# PF4_DSPBypass.net
KiCad netlist of a schematic drawn in Altium Designer
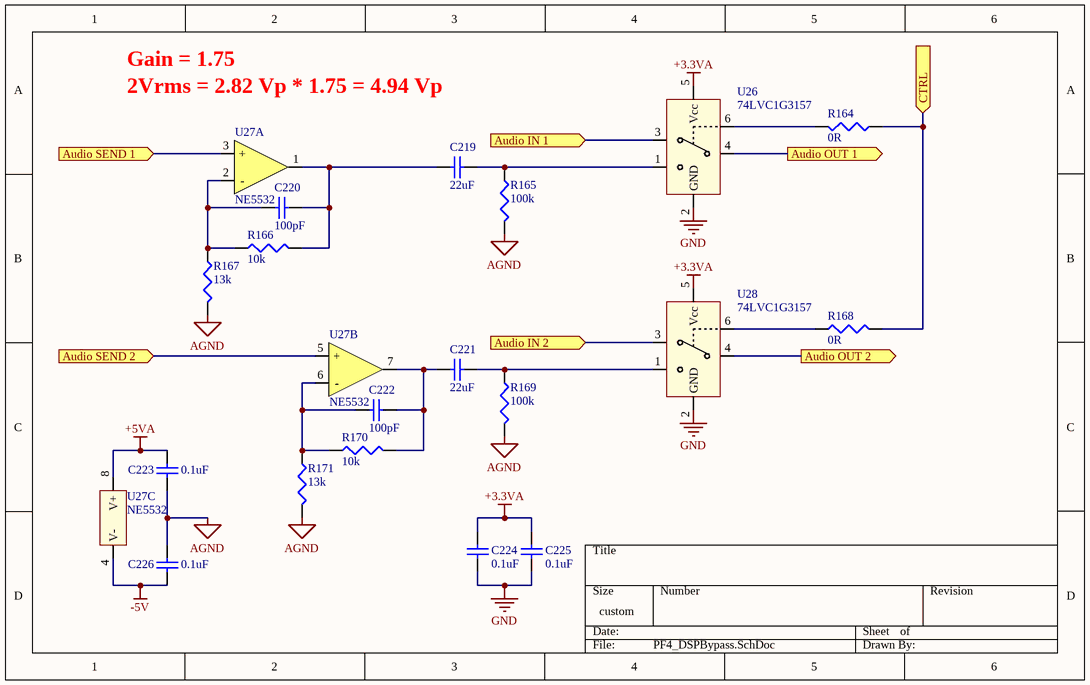
[diagram p0: PF4_DSPBypass.SchDoc]

(export (version "E")
  (design (tool "Eeschema 10.0.6"))
  (components
    (comp (ref "C219")
      (value "22uF")
      (footprint "CAPC1608X08")
      (description "Capacitor (Semiconductor SIM Model)")
      (libsource (lib "Michel") (part "Cap Semi"))
    )
    (comp (ref "C220")
      (value "100pF")
      (footprint "CAPC1608X08")
      (description "Capacitor (Semiconductor SIM Model)")
      (libsource (lib "Michel") (part "Cap Semi"))
    )
    (comp (ref "C221")
      (value "22uF")
      (footprint "CAPC1608X08")
      (description "Capacitor (Semiconductor SIM Model)")
      (libsource (lib "Michel") (part "Cap Semi"))
    )
    (comp (ref "C222")
      (value "100pF")
      (footprint "CAPC1608X08")
      (description "Capacitor (Semiconductor SIM Model)")
      (libsource (lib "Michel") (part "Cap Semi"))
    )
    (comp (ref "C223")
      (value "0.1uF")
      (footprint "CAPC1608X08")
      (description "Capacitor (Semiconductor SIM Model)")
      (libsource (lib "Michel") (part "Cap Semi"))
    )
    (comp (ref "C224")
      (value "0.1uF")
      (footprint "CAPC1608X08")
      (description "Capacitor (Semiconductor SIM Model)")
      (libsource (lib "Michel") (part "Cap Semi"))
    )
    (comp (ref "C225")
      (value "0.1uF")
      (footprint "CAPC1608X08")
      (description "Capacitor (Semiconductor SIM Model)")
      (libsource (lib "Michel") (part "Cap Semi"))
    )
    (comp (ref "C226")
      (value "0.1uF")
      (footprint "CAPC1608X08")
      (description "Capacitor (Semiconductor SIM Model)")
      (libsource (lib "Michel") (part "Cap Semi"))
    )
    (comp (ref "R164")
      (value "0R")
      (footprint "RESC1608X05")
      (description "Resistor")
      (libsource (lib "Michel") (part "Res3"))
    )
    (comp (ref "R165")
      (value "100k")
      (footprint "RESC1608X05")
      (description "Resistor")
      (libsource (lib "Michel") (part "Res3"))
    )
    (comp (ref "R166")
      (value "10k")
      (footprint "RESC1608X05")
      (description "Resistor")
      (libsource (lib "Michel") (part "Res3"))
    )
    (comp (ref "R167")
      (value "13k")
      (footprint "RESC1608X05")
      (description "Resistor")
      (libsource (lib "Michel") (part "Res3"))
    )
    (comp (ref "R168")
      (value "0R")
      (footprint "RESC1608X05")
      (description "Resistor")
      (libsource (lib "Michel") (part "Res3"))
    )
    (comp (ref "R169")
      (value "100k")
      (footprint "RESC1608X05")
      (description "Resistor")
      (libsource (lib "Michel") (part "Res3"))
    )
    (comp (ref "R170")
      (value "10k")
      (footprint "RESC1608X05")
      (description "Resistor")
      (libsource (lib "Michel") (part "Res3"))
    )
    (comp (ref "R171")
      (value "13k")
      (footprint "RESC1608X05")
      (description "Resistor")
      (libsource (lib "Michel") (part "Res3"))
    )
    (comp (ref "U26")
      (value "74LVC1G3157")
      (footprint "DBV6-M")
      (description "Single 2:1 Multiplexer")
      (libsource (lib "Michel") (part "74LVC1G3157"))
    )
    (comp (ref "U27")
      (value "NE5532")
      (footprint "D8-M")
      (description "Dual Audio OpAmp")
      (libsource (lib "Michel") (part "NE5532"))
    )
    (comp (ref "U28")
      (value "74LVC1G3157")
      (footprint "DBV6-M")
      (description "Single 2:1 Multiplexer")
      (libsource (lib "Michel") (part "74LVC1G3157"))
    )
  )
  (nets
    (net (code "1") (name "+3.3VA") (class "Default")
      (node (ref "C224") (pin "1") (pinfunction "1_1") (pintype "passive"))
      (node (ref "C225") (pin "1") (pinfunction "1_1") (pintype "passive"))
      (node (ref "U26") (pin "5") (pinfunction "Vcc_5") (pintype "power_in"))
      (node (ref "U28") (pin "5") (pinfunction "Vcc_5") (pintype "power_in"))
    )
    (net (code "2") (name "+5VA") (class "Default")
      (node (ref "C223") (pin "1") (pinfunction "1_1") (pintype "passive"))
      (node (ref "U27") (pin "8") (pinfunction "V+_8") (pintype "power_in"))
    )
    (net (code "3") (name "-5V") (class "Default")
      (node (ref "C226") (pin "2") (pinfunction "2_2") (pintype "passive"))
      (node (ref "U27") (pin "4") (pinfunction "V-_4") (pintype "power_in"))
    )
    (net (code "4") (name "/Audio IN 1") (class "Default")
      (node (ref "U26") (pin "3") (pinfunction "B1_3") (pintype "passive"))
    )
    (net (code "5") (name "/Audio IN 2") (class "Default")
      (node (ref "U28") (pin "3") (pinfunction "B1_3") (pintype "passive"))
    )
    (net (code "6") (name "/Audio OUT 1") (class "Default")
      (node (ref "U26") (pin "4") (pinfunction "A_4") (pintype "passive"))
    )
    (net (code "7") (name "/Audio OUT 2") (class "Default")
      (node (ref "U28") (pin "4") (pinfunction "A_4") (pintype "passive"))
    )
    (net (code "8") (name "/Audio SEND 1") (class "Default")
      (node (ref "U27") (pin "3") (pinfunction "+_3") (pintype "passive"))
    )
    (net (code "9") (name "/Audio SEND 2") (class "Default")
      (node (ref "U27") (pin "5") (pinfunction "+_5") (pintype "passive"))
    )
    (net (code "10") (name "/CTRL") (class "Default")
      (node (ref "R164") (pin "1") (pinfunction "1_1") (pintype "passive"))
      (node (ref "R168") (pin "2") (pinfunction "2_2") (pintype "passive"))
    )
    (net (code "11") (name "AGND") (class "Default")
      (node (ref "C223") (pin "2") (pinfunction "2_2") (pintype "passive"))
      (node (ref "C226") (pin "1") (pinfunction "1_1") (pintype "passive"))
      (node (ref "R165") (pin "2") (pinfunction "2_2") (pintype "passive"))
      (node (ref "R167") (pin "2") (pinfunction "2_2") (pintype "passive"))
      (node (ref "R169") (pin "2") (pinfunction "2_2") (pintype "passive"))
      (node (ref "R171") (pin "2") (pinfunction "2_2") (pintype "passive"))
    )
    (net (code "12") (name "GND") (class "Default")
      (node (ref "C224") (pin "2") (pinfunction "2_2") (pintype "passive"))
      (node (ref "C225") (pin "2") (pinfunction "2_2") (pintype "passive"))
      (node (ref "U26") (pin "2") (pinfunction "GND_2") (pintype "power_in"))
      (node (ref "U28") (pin "2") (pinfunction "GND_2") (pintype "power_in"))
    )
    (net (code "13") (name "Net-(U26-B2)") (class "Default")
      (node (ref "C219") (pin "1") (pinfunction "1_1") (pintype "passive"))
      (node (ref "R165") (pin "1") (pinfunction "1_1") (pintype "passive"))
      (node (ref "U26") (pin "1") (pinfunction "B2_1") (pintype "passive"))
    )
    (net (code "14") (name "Net-(U26-S)") (class "Default")
      (node (ref "R164") (pin "2") (pinfunction "2_2") (pintype "passive"))
      (node (ref "U26") (pin "6") (pinfunction "S_6") (pintype "passive"))
    )
    (net (code "15") (name "Net-(U27A--)") (class "Default")
      (node (ref "C220") (pin "1") (pinfunction "1_1") (pintype "passive"))
      (node (ref "R166") (pin "1") (pinfunction "1_1") (pintype "passive"))
      (node (ref "R167") (pin "1") (pinfunction "1_1") (pintype "passive"))
      (node (ref "U27") (pin "2") (pinfunction "-_2") (pintype "passive"))
    )
    (net (code "16") (name "Net-(U27A-OUT)") (class "Default")
      (node (ref "C219") (pin "2") (pinfunction "2_2") (pintype "passive"))
      (node (ref "C220") (pin "2") (pinfunction "2_2") (pintype "passive"))
      (node (ref "R166") (pin "2") (pinfunction "2_2") (pintype "passive"))
      (node (ref "U27") (pin "1") (pinfunction "OUT_1") (pintype "passive"))
    )
    (net (code "17") (name "Net-(U27B--)") (class "Default")
      (node (ref "C222") (pin "1") (pinfunction "1_1") (pintype "passive"))
      (node (ref "R170") (pin "1") (pinfunction "1_1") (pintype "passive"))
      (node (ref "R171") (pin "1") (pinfunction "1_1") (pintype "passive"))
      (node (ref "U27") (pin "6") (pinfunction "-_6") (pintype "passive"))
    )
    (net (code "18") (name "Net-(U27B-OUT)") (class "Default")
      (node (ref "C221") (pin "2") (pinfunction "2_2") (pintype "passive"))
      (node (ref "C222") (pin "2") (pinfunction "2_2") (pintype "passive"))
      (node (ref "R170") (pin "2") (pinfunction "2_2") (pintype "passive"))
      (node (ref "U27") (pin "7") (pinfunction "OUT_7") (pintype "passive"))
    )
    (net (code "19") (name "Net-(U28-B2)") (class "Default")
      (node (ref "C221") (pin "1") (pinfunction "1_1") (pintype "passive"))
      (node (ref "R169") (pin "1") (pinfunction "1_1") (pintype "passive"))
      (node (ref "U28") (pin "1") (pinfunction "B2_1") (pintype "passive"))
    )
    (net (code "20") (name "Net-(U28-S)") (class "Default")
      (node (ref "R168") (pin "1") (pinfunction "1_1") (pintype "passive"))
      (node (ref "U28") (pin "6") (pinfunction "S_6") (pintype "passive"))
    )
  )
)
